# Knob.net
KiCad netlist of a schematic drawn in EAGLE
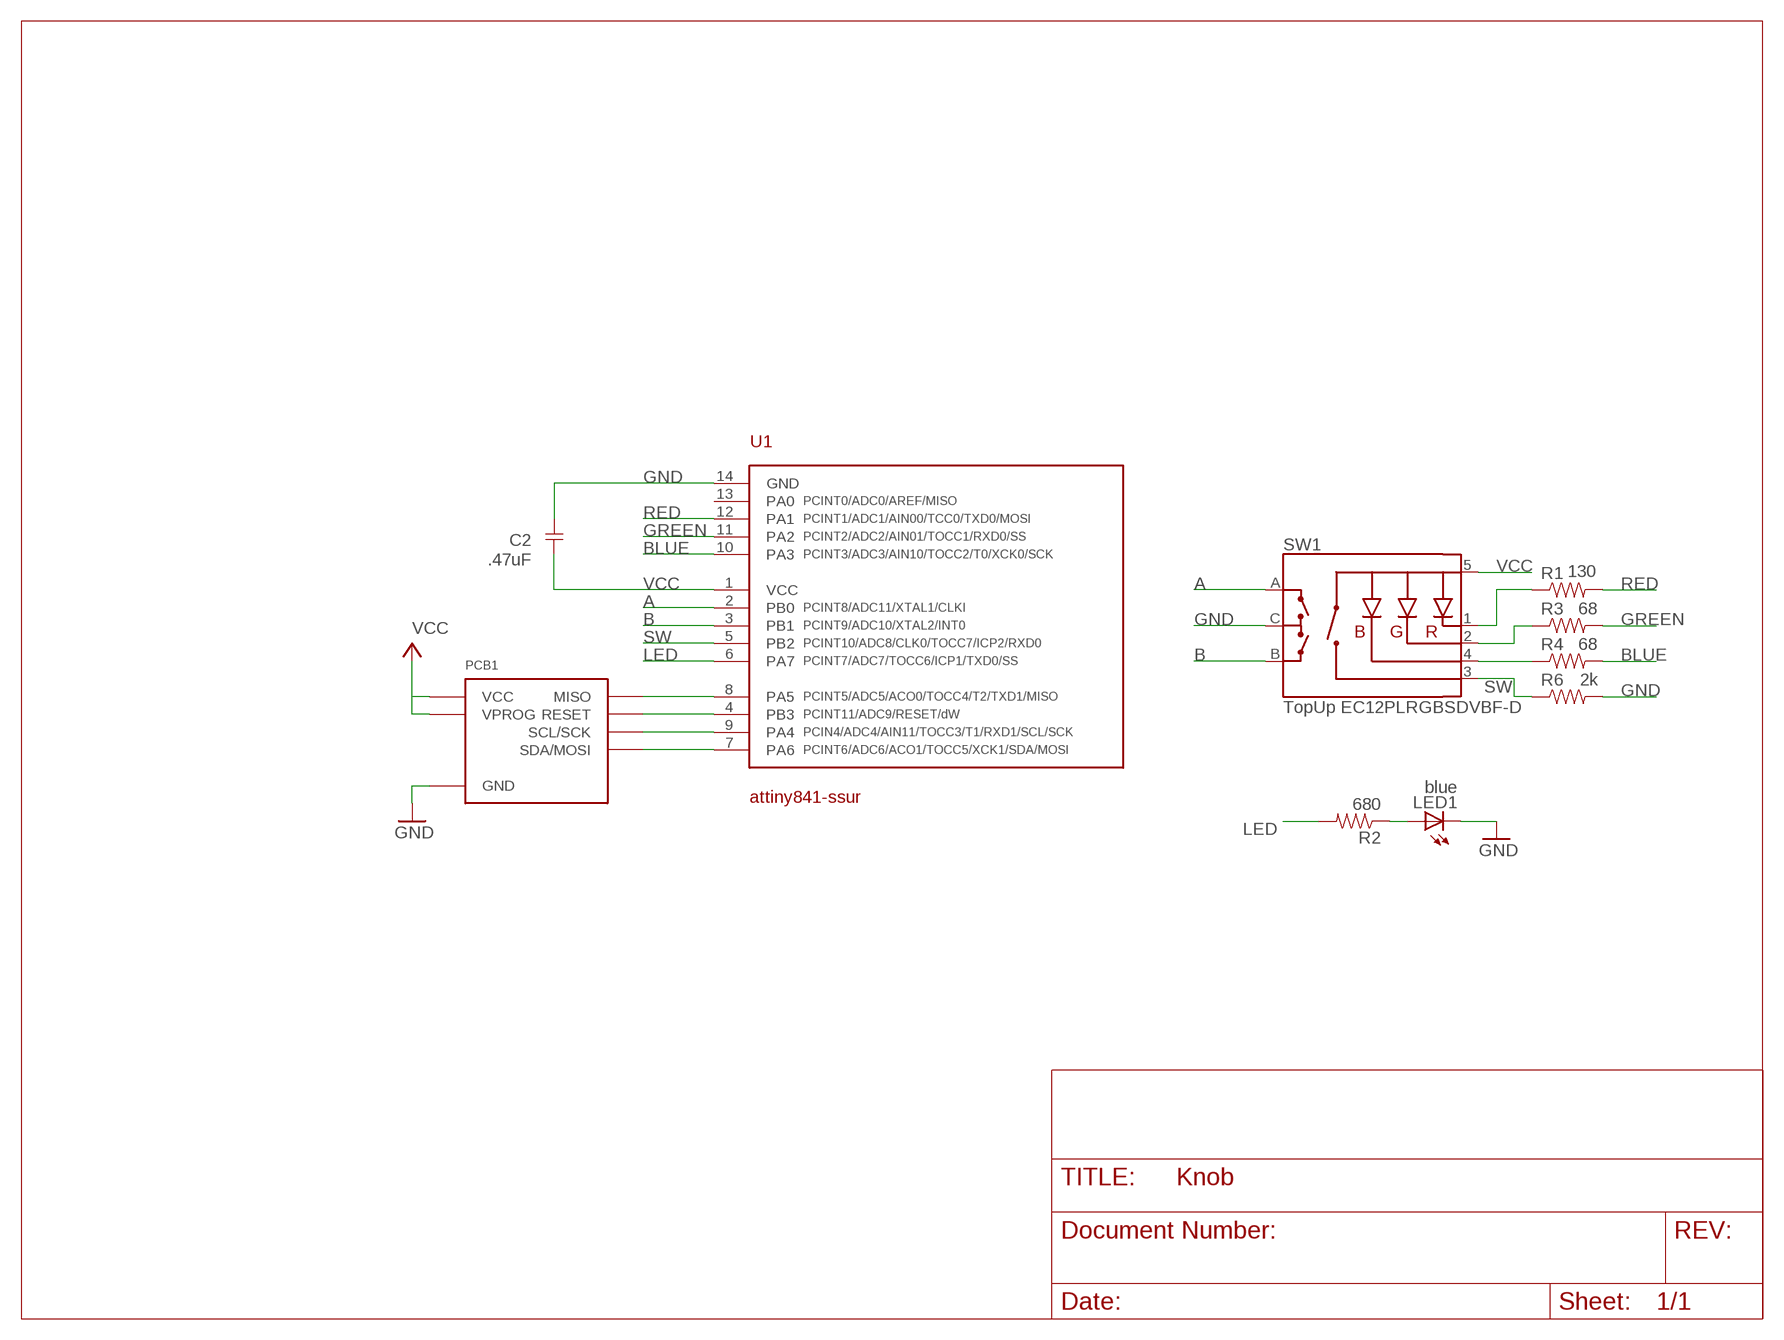
[diagram p0: schematic, sheet 1]

(export (version "E")
  (design (tool "Eeschema 10.0.6"))
  (components
    (comp (ref "C2")
      (value ".47uF")
      (footprint "eagle-import:0805")
      (libsource (lib "eagle-import") (part "CAPACITOR"))
    )
    (comp (ref "LED1")
      (value "blue")
      (footprint "eagle-import:0805-LED")
      (fields (field (name "PARTNUM") "LTST-C171TBKT"))
      (libsource (lib "eagle-import") (part "LED-0805-BLUE"))
    )
    (comp (ref "PCB1")
      (value "MAGDEVICE-V2")
      (footprint "eagle-import:MAGDEVICE-V2")
      (libsource (lib "eagle-import") (part "MAGDEVICE-V2"))
    )
    (comp (ref "R1")
      (value "130")
      (footprint "eagle-import:0805")
      (libsource (lib "eagle-import") (part "RESISTOR"))
    )
    (comp (ref "R2")
      (value "680")
      (footprint "eagle-import:0805")
      (libsource (lib "eagle-import") (part "RESISTOR"))
    )
    (comp (ref "R3")
      (value "68")
      (footprint "eagle-import:0805")
      (libsource (lib "eagle-import") (part "RESISTOR"))
    )
    (comp (ref "R4")
      (value "68")
      (footprint "eagle-import:0805")
      (libsource (lib "eagle-import") (part "RESISTOR"))
    )
    (comp (ref "R6")
      (value "2k")
      (footprint "eagle-import:0805")
      (libsource (lib "eagle-import") (part "RESISTOR"))
    )
    (comp (ref "SW1")
      (value "TopUp EC12PLRGBSDVBF-D")
      (footprint "eagle-import:ENCODER_LED_3")
      (libsource (lib "eagle-import") (part "ENCODER_RGB_CA"))
    )
    (comp (ref "U1")
      (value "attiny841-ssur")
      (footprint "eagle-import:SOIC14")
      (libsource (lib "eagle-import") (part "ATTINY841"))
    )
  )
  (nets
    (net (code "1") (name "/A") (class "Default")
      (node (ref "SW1") (pin "A") (pinfunction "A_A") (pintype "bidirectional"))
      (node (ref "U1") (pin "2") (pinfunction "PB0_2") (pintype "bidirectional"))
    )
    (net (code "2") (name "/B") (class "Default")
      (node (ref "SW1") (pin "B") (pinfunction "B_B") (pintype "bidirectional"))
      (node (ref "U1") (pin "3") (pinfunction "PB1_3") (pintype "bidirectional"))
    )
    (net (code "3") (name "/BLUE") (class "Default")
      (node (ref "R4") (pin "2") (pinfunction "2_2") (pintype "passive"))
      (node (ref "U1") (pin "10") (pinfunction "PA3_10") (pintype "bidirectional"))
    )
    (net (code "4") (name "/GREEN") (class "Default")
      (node (ref "R3") (pin "2") (pinfunction "2_2") (pintype "passive"))
      (node (ref "U1") (pin "11") (pinfunction "PA2_11") (pintype "bidirectional"))
    )
    (net (code "5") (name "/LED") (class "Default")
      (node (ref "R2") (pin "2") (pinfunction "2_2") (pintype "passive"))
      (node (ref "U1") (pin "6") (pinfunction "PA7_6") (pintype "bidirectional"))
    )
    (net (code "6") (name "/RED") (class "Default")
      (node (ref "R1") (pin "2") (pinfunction "2_2") (pintype "passive"))
      (node (ref "U1") (pin "12") (pinfunction "PA1_12") (pintype "bidirectional"))
    )
    (net (code "7") (name "/SW") (class "Default")
      (node (ref "R6") (pin "1") (pinfunction "1_1") (pintype "passive"))
      (node (ref "SW1") (pin "3") (pinfunction "SW_3") (pintype "passive"))
      (node (ref "U1") (pin "5") (pinfunction "PB2_5") (pintype "bidirectional"))
    )
    (net (code "8") (name "GND") (class "Default")
      (node (ref "C2") (pin "2") (pinfunction "2_2") (pintype "passive"))
      (node (ref "LED1") (pin "C") (pinfunction "C_C") (pintype "passive"))
      (node (ref "PCB1") (pin "GND") (pinfunction "GND_GND") (pintype "bidirectional"))
      (node (ref "R6") (pin "2") (pinfunction "2_2") (pintype "passive"))
      (node (ref "SW1") (pin "C") (pinfunction "C_C") (pintype "bidirectional"))
      (node (ref "U1") (pin "14") (pinfunction "GND_14") (pintype "bidirectional"))
    )
    (net (code "9") (name "Net-(LED1-PadA)") (class "Default")
      (node (ref "LED1") (pin "A") (pinfunction "A_A") (pintype "passive"))
      (node (ref "R2") (pin "1") (pinfunction "1_1") (pintype "passive"))
    )
    (net (code "10") (name "Net-(PCB1-SCL{slash}SCK)") (class "Default")
      (node (ref "PCB1") (pin "SCL") (pinfunction "SCL/SCK_SCL") (pintype "bidirectional"))
      (node (ref "U1") (pin "9") (pinfunction "PA4_9") (pintype "bidirectional"))
    )
    (net (code "11") (name "Net-(PCB1-SDA{slash}MOSI)") (class "Default")
      (node (ref "PCB1") (pin "SDA") (pinfunction "SDA/MOSI_SDA") (pintype "bidirectional"))
      (node (ref "U1") (pin "7") (pinfunction "PA6_7") (pintype "bidirectional"))
    )
    (net (code "12") (name "Net-(SW1--B)") (class "Default")
      (node (ref "R4") (pin "1") (pinfunction "1_1") (pintype "passive"))
      (node (ref "SW1") (pin "4") (pinfunction "-B_4") (pintype "passive"))
    )
    (net (code "13") (name "Net-(SW1--G)") (class "Default")
      (node (ref "R3") (pin "1") (pinfunction "1_1") (pintype "passive"))
      (node (ref "SW1") (pin "2") (pinfunction "-G_2") (pintype "passive"))
    )
    (net (code "14") (name "Net-(SW1--R)") (class "Default")
      (node (ref "R1") (pin "1") (pinfunction "1_1") (pintype "passive"))
      (node (ref "SW1") (pin "1") (pinfunction "-R_1") (pintype "passive"))
    )
    (net (code "15") (name "Net-(U1-PA5)") (class "Default")
      (node (ref "PCB1") (pin "MISO") (pinfunction "MISO_MISO") (pintype "bidirectional"))
      (node (ref "U1") (pin "8") (pinfunction "PA5_8") (pintype "bidirectional"))
    )
    (net (code "16") (name "Net-(U1-PB3)") (class "Default")
      (node (ref "PCB1") (pin "RESET") (pinfunction "RESET_RESET") (pintype "bidirectional"))
      (node (ref "U1") (pin "4") (pinfunction "PB3_4") (pintype "bidirectional"))
    )
    (net (code "17") (name "VCC") (class "Default")
      (node (ref "C2") (pin "1") (pinfunction "1_1") (pintype "passive"))
      (node (ref "PCB1") (pin "VCC") (pinfunction "VCC_VCC") (pintype "bidirectional"))
      (node (ref "PCB1") (pin "VPROG") (pinfunction "VPROG_VPROG") (pintype "bidirectional"))
      (node (ref "SW1") (pin "5") (pinfunction "+_5") (pintype "passive"))
      (node (ref "U1") (pin "1") (pinfunction "VCC_1") (pintype "bidirectional"))
    )
    (net (code "18") (name "unconnected-(U1-PA0-Pad13)") (class "Default")
      (node (ref "U1") (pin "13") (pinfunction "PA0_13") (pintype "bidirectional"))
    )
  )
)
